# Mecanumbot_Power_Board.net
KiCad netlist of a schematic drawn in EAGLE
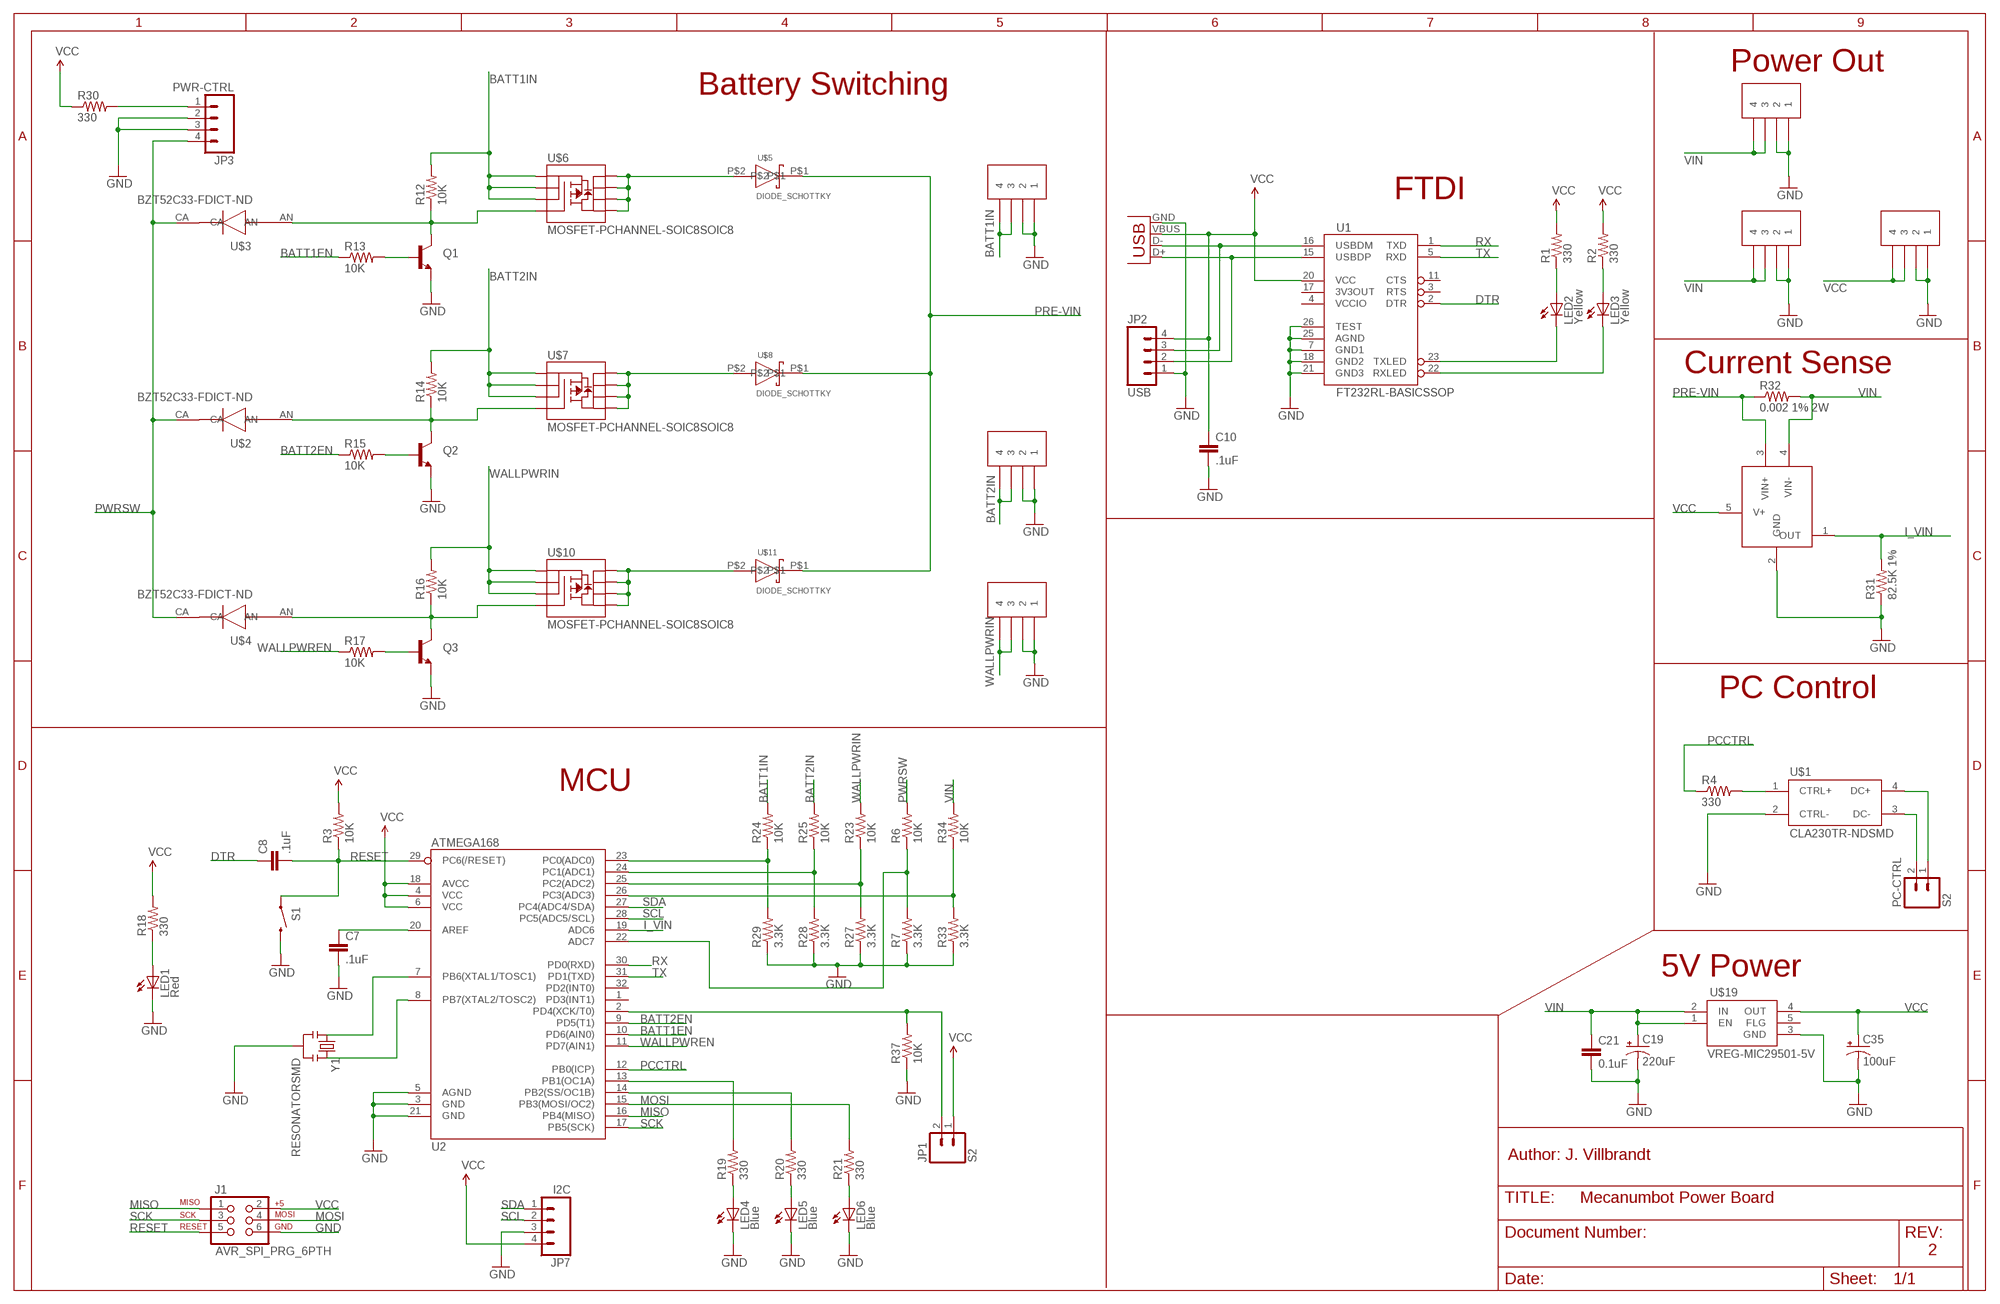
[diagram p0: schematic, sheet 1]

(export (version "E")
  (design (tool "Eeschema 10.0.6"))
  (components
    (comp (ref "C7")
      (value ".1uF")
      (footprint "eagle-import:0603-CAP")
      (libsource (lib "eagle-import") (part "CAP0603-CAP"))
    )
    (comp (ref "C8")
      (value ".1uF")
      (footprint "eagle-import:0603-CAP")
      (libsource (lib "eagle-import") (part "CAP0603-CAP"))
    )
    (comp (ref "C10")
      (value ".1uF")
      (footprint "eagle-import:0603-CAP")
      (libsource (lib "eagle-import") (part "CAP0603-CAP"))
    )
    (comp (ref "C19")
      (value "220uF")
      (footprint "eagle-import:CPOL-RADIAL-1000UF-25V")
      (libsource (lib "eagle-import") (part "SparkFun2_CAP_POLPTH4"))
    )
    (comp (ref "C21")
      (value "0.1uF")
      (footprint "eagle-import:1206")
      (libsource (lib "eagle-import") (part "SparkFun2_CAP1206"))
    )
    (comp (ref "C35")
      (value "100uF")
      (footprint "eagle-import:EIA3216")
      (libsource (lib "eagle-import") (part "CAP_POL1206"))
    )
    (comp (ref "J1")
      (value "AVR_SPI_PRG_6PTH")
      (footprint "eagle-import:2X3")
      (libsource (lib "eagle-import") (part "AVR_SPI_PRG_6PTH"))
    )
    (comp (ref "JP1")
      (value "S2")
      (footprint "eagle-import:1X02")
      (libsource (lib "eagle-import") (part "M02PTH"))
    )
    (comp (ref "JP2")
      (value "USB")
      (footprint "eagle-import:1X04")
      (libsource (lib "eagle-import") (part "M04PTH"))
    )
    (comp (ref "JP3")
      (value "PWR-CTRL")
      (footprint "eagle-import:1X04")
      (libsource (lib "eagle-import") (part "M04PTH"))
    )
    (comp (ref "JP7")
      (value "I2C")
      (footprint "eagle-import:1X04")
      (libsource (lib "eagle-import") (part "M04PTH"))
    )
    (comp (ref "LED1")
      (value "Red")
      (footprint "eagle-import:LED-0603")
      (libsource (lib "eagle-import") (part "LED0603"))
    )
    (comp (ref "LED2")
      (value "Yellow")
      (footprint "eagle-import:LED-0603")
      (libsource (lib "eagle-import") (part "LED0603"))
    )
    (comp (ref "LED3")
      (value "Yellow")
      (footprint "eagle-import:LED-0603")
      (libsource (lib "eagle-import") (part "LED0603"))
    )
    (comp (ref "LED4")
      (value "Blue")
      (footprint "eagle-import:LED-0603")
      (libsource (lib "eagle-import") (part "LED0603"))
    )
    (comp (ref "LED5")
      (value "Blue")
      (footprint "eagle-import:LED-0603")
      (libsource (lib "eagle-import") (part "LED0603"))
    )
    (comp (ref "LED6")
      (value "Blue")
      (footprint "eagle-import:LED-0603")
      (libsource (lib "eagle-import") (part "LED0603"))
    )
    (comp (ref "PC-CTRL")
      (value "S2")
      (footprint "eagle-import:1X02")
      (libsource (lib "eagle-import") (part "M02PTH"))
    )
    (comp (ref "Q1")
      (value "TRANSISTOR_NPNSOT23")
      (footprint "eagle-import:SOT23")
      (libsource (lib "eagle-import") (part "TRANSISTOR_NPNSOT23"))
    )
    (comp (ref "Q2")
      (value "TRANSISTOR_NPNSOT23")
      (footprint "eagle-import:SOT23")
      (libsource (lib "eagle-import") (part "TRANSISTOR_NPNSOT23"))
    )
    (comp (ref "Q3")
      (value "TRANSISTOR_NPNSOT23")
      (footprint "eagle-import:SOT23")
      (libsource (lib "eagle-import") (part "TRANSISTOR_NPNSOT23"))
    )
    (comp (ref "R1")
      (value "330")
      (footprint "eagle-import:0603-RES")
      (libsource (lib "eagle-import") (part "RESISTOR0603-RES"))
    )
    (comp (ref "R2")
      (value "330")
      (footprint "eagle-import:0603-RES")
      (libsource (lib "eagle-import") (part "RESISTOR0603-RES"))
    )
    (comp (ref "R3")
      (value "10K")
      (footprint "eagle-import:0603-RES")
      (libsource (lib "eagle-import") (part "RESISTOR0603-RES"))
    )
    (comp (ref "R4")
      (value "330")
      (footprint "eagle-import:0603-RES")
      (libsource (lib "eagle-import") (part "RESISTOR0603-RES"))
    )
    (comp (ref "R6")
      (value "10K")
      (footprint "eagle-import:0603-RES")
      (libsource (lib "eagle-import") (part "RESISTOR0603-RES"))
    )
    (comp (ref "R7")
      (value "3.3K")
      (footprint "eagle-import:0603-RES")
      (libsource (lib "eagle-import") (part "RESISTOR0603-RES"))
    )
    (comp (ref "R12")
      (value "10K")
      (footprint "eagle-import:0603-RES")
      (libsource (lib "eagle-import") (part "RESISTOR0603-RES"))
    )
    (comp (ref "R13")
      (value "10K")
      (footprint "eagle-import:0603-RES")
      (libsource (lib "eagle-import") (part "RESISTOR0603-RES"))
    )
    (comp (ref "R14")
      (value "10K")
      (footprint "eagle-import:0603-RES")
      (libsource (lib "eagle-import") (part "RESISTOR0603-RES"))
    )
    (comp (ref "R15")
      (value "10K")
      (footprint "eagle-import:0603-RES")
      (libsource (lib "eagle-import") (part "RESISTOR0603-RES"))
    )
    (comp (ref "R16")
      (value "10K")
      (footprint "eagle-import:0603-RES")
      (libsource (lib "eagle-import") (part "RESISTOR0603-RES"))
    )
    (comp (ref "R17")
      (value "10K")
      (footprint "eagle-import:0603-RES")
      (libsource (lib "eagle-import") (part "RESISTOR0603-RES"))
    )
    (comp (ref "R18")
      (value "330")
      (footprint "eagle-import:0603-RES")
      (libsource (lib "eagle-import") (part "RESISTOR0603-RES"))
    )
    (comp (ref "R19")
      (value "330")
      (footprint "eagle-import:0603-RES")
      (libsource (lib "eagle-import") (part "RESISTOR0603-RES"))
    )
    (comp (ref "R20")
      (value "330")
      (footprint "eagle-import:0603-RES")
      (libsource (lib "eagle-import") (part "RESISTOR0603-RES"))
    )
    (comp (ref "R21")
      (value "330")
      (footprint "eagle-import:0603-RES")
      (libsource (lib "eagle-import") (part "RESISTOR0603-RES"))
    )
    (comp (ref "R23")
      (value "10K")
      (footprint "eagle-import:0603-RES")
      (libsource (lib "eagle-import") (part "RESISTOR0603-RES"))
    )
    (comp (ref "R24")
      (value "10K")
      (footprint "eagle-import:0603-RES")
      (libsource (lib "eagle-import") (part "RESISTOR0603-RES"))
    )
    (comp (ref "R25")
      (value "10K")
      (footprint "eagle-import:0603-RES")
      (libsource (lib "eagle-import") (part "RESISTOR0603-RES"))
    )
    (comp (ref "R27")
      (value "3.3K")
      (footprint "eagle-import:0603-RES")
      (libsource (lib "eagle-import") (part "RESISTOR0603-RES"))
    )
    (comp (ref "R28")
      (value "3.3K")
      (footprint "eagle-import:0603-RES")
      (libsource (lib "eagle-import") (part "RESISTOR0603-RES"))
    )
    (comp (ref "R29")
      (value "3.3K")
      (footprint "eagle-import:0603-RES")
      (libsource (lib "eagle-import") (part "RESISTOR0603-RES"))
    )
    (comp (ref "R30")
      (value "330")
      (footprint "eagle-import:0603-RES")
      (libsource (lib "eagle-import") (part "RESISTOR0603-RES"))
    )
    (comp (ref "R31")
      (value "82.5K 1%")
      (footprint "eagle-import:0603-RES")
      (libsource (lib "eagle-import") (part "RESISTOR0603-RES"))
    )
    (comp (ref "R32")
      (value "0.002 1% 2W")
      (footprint "eagle-import:R2512")
      (libsource (lib "eagle-import") (part "RESISTOR2512"))
    )
    (comp (ref "R33")
      (value "3.3K")
      (footprint "eagle-import:0603-RES")
      (libsource (lib "eagle-import") (part "RESISTOR0603-RES"))
    )
    (comp (ref "R34")
      (value "10K")
      (footprint "eagle-import:0603-RES")
      (libsource (lib "eagle-import") (part "RESISTOR0603-RES"))
    )
    (comp (ref "R37")
      (value "10K")
      (footprint "eagle-import:0603-RES")
      (libsource (lib "eagle-import") (part "RESISTOR0603-RES"))
    )
    (comp (ref "S1")
      (value "reset")
      (footprint "eagle-import:TACTILE_SWITCH_SMD")
      (libsource (lib "eagle-import") (part "SWITCH-MOMENTARY-2SMD"))
    )
    (comp (ref "U$1")
      (value "CLA230TR-NDSMD")
      (footprint "eagle-import:4-SOP")
      (libsource (lib "eagle-import") (part "CLA230TR-NDSMD"))
    )
    (comp (ref "U$2")
      (value "BZT52C33-FDICT-ND")
      (footprint "eagle-import:SOD-123")
      (libsource (lib "eagle-import") (part "BZT52C33-FDICT-ND"))
    )
    (comp (ref "U$3")
      (value "BZT52C33-FDICT-ND")
      (footprint "eagle-import:SOD-123")
      (libsource (lib "eagle-import") (part "BZT52C33-FDICT-ND"))
    )
    (comp (ref "U$4")
      (value "BZT52C33-FDICT-ND")
      (footprint "eagle-import:SOD-123")
      (libsource (lib "eagle-import") (part "BZT52C33-FDICT-ND"))
    )
    (comp (ref "U$5")
      (value "DIODE_SCHOTTKY")
      (footprint "eagle-import:DO214AB")
      (libsource (lib "eagle-import") (part "DIODE_SCHOTTKY"))
    )
    (comp (ref "U$6")
      (value "MOSFET-PCHANNEL-SOIC8SOIC8")
      (footprint "eagle-import:SO08")
      (libsource (lib "eagle-import") (part "MOSFET-PCHANNEL-SOIC8SOIC8"))
    )
    (comp (ref "U$7")
      (value "MOSFET-PCHANNEL-SOIC8SOIC8")
      (footprint "eagle-import:SO08")
      (libsource (lib "eagle-import") (part "MOSFET-PCHANNEL-SOIC8SOIC8"))
    )
    (comp (ref "U$8")
      (value "DIODE_SCHOTTKY")
      (footprint "eagle-import:DO214AB")
      (libsource (lib "eagle-import") (part "DIODE_SCHOTTKY"))
    )
    (comp (ref "U$10")
      (value "MOSFET-PCHANNEL-SOIC8SOIC8")
      (footprint "eagle-import:SO08")
      (libsource (lib "eagle-import") (part "MOSFET-PCHANNEL-SOIC8SOIC8"))
    )
    (comp (ref "U$11")
      (value "DIODE_SCHOTTKY")
      (footprint "eagle-import:DO214AB")
      (libsource (lib "eagle-import") (part "DIODE_SCHOTTKY"))
    )
    (comp (ref "U$12")
      (value "TERMINAL-4MINIFIT-JR")
      (footprint "eagle-import:MINIFITJR-RGT-4")
      (libsource (lib "eagle-import") (part "TERMINAL-4MINIFIT-JR"))
    )
    (comp (ref "U$13")
      (value "TERMINAL-4MINIFIT-JR")
      (footprint "eagle-import:MINIFITJR-RGT-4")
      (libsource (lib "eagle-import") (part "TERMINAL-4MINIFIT-JR"))
    )
    (comp (ref "U$14")
      (value "TERMINAL-4MINIFIT-JR")
      (footprint "eagle-import:MINIFITJR-RGT-4")
      (libsource (lib "eagle-import") (part "TERMINAL-4MINIFIT-JR"))
    )
    (comp (ref "U$16")
      (value "TERMINAL-4MINIFIT-JR")
      (footprint "eagle-import:MINIFITJR-RGT-4")
      (libsource (lib "eagle-import") (part "TERMINAL-4MINIFIT-JR"))
    )
    (comp (ref "U$17")
      (value "TERMINAL-4MINIFIT-JR")
      (footprint "eagle-import:MINIFITJR-RGT-4")
      (libsource (lib "eagle-import") (part "TERMINAL-4MINIFIT-JR"))
    )
    (comp (ref "U$18")
      (value "TERMINAL-4MINIFIT-JR")
      (footprint "eagle-import:MINIFITJR-RGT-4")
      (libsource (lib "eagle-import") (part "TERMINAL-4MINIFIT-JR"))
    )
    (comp (ref "U$19")
      (value "VREG-MIC29501-5V")
      (footprint "eagle-import:TO263-5")
      (libsource (lib "eagle-import") (part "VREG-MIC29501-5V"))
    )
    (comp (ref "U$20")
      (value "INA139/169SOT23-5")
      (footprint "eagle-import:SOT23-5")
      (libsource (lib "eagle-import") (part "INA139/169SOT23-5"))
    )
    (comp (ref "U1")
      (value "FT232RL-BASICSSOP")
      (footprint "eagle-import:SSOP28DB")
      (libsource (lib "eagle-import") (part "FT232RL-BASICSSOP"))
    )
    (comp (ref "U2")
      (value "ATMEGA168")
      (footprint "eagle-import:TQFP32-08")
      (libsource (lib "eagle-import") (part "ATMEGA168"))
    )
    (comp (ref "X1")
      (value "USBSMD")
      (footprint "eagle-import:USB-MINIB")
      (libsource (lib "eagle-import") (part "USBSMD"))
    )
    (comp (ref "Y1")
      (value "RESONATORSMD")
      (footprint "eagle-import:RESONATOR-SMD")
      (libsource (lib "eagle-import") (part "RESONATORSMD"))
    )
  )
  (nets
    (net (code "1") (name "/BATT1EN") (class "Default")
      (node (ref "R13") (pin "1") (pinfunction "1_1") (pintype "passive"))
      (node (ref "U2") (pin "10") (pinfunction "PD6(AIN0)_10") (pintype "bidirectional"))
    )
    (net (code "2") (name "/BATT1IN") (class "Default")
      (node (ref "R12") (pin "2") (pinfunction "2_2") (pintype "passive"))
      (node (ref "R24") (pin "2") (pinfunction "2_2") (pintype "passive"))
      (node (ref "U$12") (pin "3") (pinfunction "3_3") (pintype "bidirectional"))
      (node (ref "U$12") (pin "4") (pinfunction "4_4") (pintype "bidirectional"))
      (node (ref "U$6") (pin "1") (pinfunction "S_1") (pintype "bidirectional"))
      (node (ref "U$6") (pin "2") (pinfunction "S_2") (pintype "bidirectional"))
      (node (ref "U$6") (pin "3") (pinfunction "S_3") (pintype "bidirectional"))
    )
    (net (code "3") (name "/BATT2EN") (class "Default")
      (node (ref "R15") (pin "1") (pinfunction "1_1") (pintype "passive"))
      (node (ref "U2") (pin "9") (pinfunction "PD5(T1)_9") (pintype "bidirectional"))
    )
    (net (code "4") (name "/BATT2IN") (class "Default")
      (node (ref "R14") (pin "2") (pinfunction "2_2") (pintype "passive"))
      (node (ref "R25") (pin "2") (pinfunction "2_2") (pintype "passive"))
      (node (ref "U$13") (pin "3") (pinfunction "3_3") (pintype "bidirectional"))
      (node (ref "U$13") (pin "4") (pinfunction "4_4") (pintype "bidirectional"))
      (node (ref "U$7") (pin "1") (pinfunction "S_1") (pintype "bidirectional"))
      (node (ref "U$7") (pin "2") (pinfunction "S_2") (pintype "bidirectional"))
      (node (ref "U$7") (pin "3") (pinfunction "S_3") (pintype "bidirectional"))
    )
    (net (code "5") (name "/DTR") (class "Default")
      (node (ref "C8") (pin "1") (pinfunction "1_1") (pintype "passive"))
      (node (ref "U1") (pin "2") (pinfunction "DTR_2") (pintype "bidirectional"))
    )
    (net (code "6") (name "/I_VIN") (class "Default")
      (node (ref "R31") (pin "2") (pinfunction "2_2") (pintype "passive"))
      (node (ref "U$20") (pin "1") (pinfunction "OUT_1") (pintype "bidirectional"))
      (node (ref "U2") (pin "19") (pinfunction "ADC6_19") (pintype "bidirectional"))
    )
    (net (code "7") (name "/MISO") (class "Default")
      (node (ref "J1") (pin "1") (pinfunction "1_1") (pintype "passive"))
      (node (ref "U2") (pin "16") (pinfunction "PB4(MISO)_16") (pintype "bidirectional"))
    )
    (net (code "8") (name "/MOSI") (class "Default")
      (node (ref "J1") (pin "4") (pinfunction "4_4") (pintype "passive"))
      (node (ref "R21") (pin "2") (pinfunction "2_2") (pintype "passive"))
      (node (ref "U2") (pin "15") (pinfunction "PB3(MOSI/OC2)_15") (pintype "bidirectional"))
    )
    (net (code "9") (name "/PCCTRL") (class "Default")
      (node (ref "R4") (pin "1") (pinfunction "1_1") (pintype "passive"))
      (node (ref "U2") (pin "12") (pinfunction "PB0(ICP)_12") (pintype "bidirectional"))
    )
    (net (code "10") (name "/PRE-VIN") (class "Default")
      (node (ref "R32") (pin "1") (pinfunction "1_1") (pintype "passive"))
      (node (ref "U$11") (pin "P$1") (pinfunction "P$2_P$1") (pintype "bidirectional"))
      (node (ref "U$20") (pin "3") (pinfunction "VIN+_3") (pintype "bidirectional"))
      (node (ref "U$5") (pin "P$1") (pinfunction "P$2_P$1") (pintype "bidirectional"))
      (node (ref "U$8") (pin "P$1") (pinfunction "P$2_P$1") (pintype "bidirectional"))
    )
    (net (code "11") (name "/PWRSW") (class "Default")
      (node (ref "JP3") (pin "4") (pinfunction "4_4") (pintype "passive"))
      (node (ref "R6") (pin "2") (pinfunction "2_2") (pintype "passive"))
      (node (ref "U$2") (pin "CA") (pinfunction "CA_CA") (pintype "bidirectional"))
      (node (ref "U$3") (pin "CA") (pinfunction "CA_CA") (pintype "bidirectional"))
      (node (ref "U$4") (pin "CA") (pinfunction "CA_CA") (pintype "bidirectional"))
    )
    (net (code "12") (name "/RESET") (class "Default")
      (node (ref "C8") (pin "2") (pinfunction "2_2") (pintype "passive"))
      (node (ref "J1") (pin "5") (pinfunction "5_5") (pintype "passive"))
      (node (ref "R3") (pin "1") (pinfunction "1_1") (pintype "passive"))
      (node (ref "S1") (pin "1") (pinfunction "1_1") (pintype "passive"))
      (node (ref "U2") (pin "29") (pinfunction "PC6(/RESET)_29") (pintype "bidirectional"))
    )
    (net (code "13") (name "/RX") (class "Default")
      (node (ref "U1") (pin "1") (pinfunction "TXD_1") (pintype "output"))
      (node (ref "U2") (pin "30") (pinfunction "PD0(RXD)_30") (pintype "bidirectional"))
    )
    (net (code "14") (name "/SCK") (class "Default")
      (node (ref "J1") (pin "3") (pinfunction "3_3") (pintype "passive"))
      (node (ref "U2") (pin "17") (pinfunction "PB5(SCK)_17") (pintype "bidirectional"))
    )
    (net (code "15") (name "/SCL") (class "Default")
      (node (ref "JP7") (pin "2") (pinfunction "2_2") (pintype "passive"))
      (node (ref "U2") (pin "28") (pinfunction "PC5(ADC5/SCL)_28") (pintype "bidirectional"))
    )
    (net (code "16") (name "/SDA") (class "Default")
      (node (ref "JP7") (pin "1") (pinfunction "1_1") (pintype "passive"))
      (node (ref "U2") (pin "27") (pinfunction "PC4(ADC4/SDA)_27") (pintype "bidirectional"))
    )
    (net (code "17") (name "/TX") (class "Default")
      (node (ref "U1") (pin "5") (pinfunction "RXD_5") (pintype "input"))
      (node (ref "U2") (pin "31") (pinfunction "PD1(TXD)_31") (pintype "bidirectional"))
    )
    (net (code "18") (name "/VCCIO") (class "Default")
      (node (ref "U1") (pin "4") (pinfunction "VCCIO_4") (pintype "power_in"))
    )
    (net (code "19") (name "/VIN") (class "Default")
      (node (ref "C19") (pin "1") (pinfunction "+_1") (pintype "passive"))
      (node (ref "C21") (pin "1") (pinfunction "1_1") (pintype "passive"))
      (node (ref "R32") (pin "2") (pinfunction "2_2") (pintype "passive"))
      (node (ref "R34") (pin "2") (pinfunction "2_2") (pintype "passive"))
      (node (ref "U$16") (pin "3") (pinfunction "3_3") (pintype "bidirectional"))
      (node (ref "U$16") (pin "4") (pinfunction "4_4") (pintype "bidirectional"))
      (node (ref "U$17") (pin "3") (pinfunction "3_3") (pintype "bidirectional"))
      (node (ref "U$17") (pin "4") (pinfunction "4_4") (pintype "bidirectional"))
      (node (ref "U$19") (pin "1") (pinfunction "EN_1") (pintype "input"))
      (node (ref "U$19") (pin "2") (pinfunction "IN_2") (pintype "input"))
      (node (ref "U$20") (pin "4") (pinfunction "VIN-_4") (pintype "bidirectional"))
    )
    (net (code "20") (name "/WALLPWREN") (class "Default")
      (node (ref "R17") (pin "1") (pinfunction "1_1") (pintype "passive"))
      (node (ref "U2") (pin "11") (pinfunction "PD7(AIN1)_11") (pintype "bidirectional"))
    )
    (net (code "21") (name "/WALLPWRIN") (class "Default")
      (node (ref "R16") (pin "2") (pinfunction "2_2") (pintype "passive"))
      (node (ref "R23") (pin "2") (pinfunction "2_2") (pintype "passive"))
      (node (ref "U$10") (pin "1") (pinfunction "S_1") (pintype "bidirectional"))
      (node (ref "U$10") (pin "2") (pinfunction "S_2") (pintype "bidirectional"))
      (node (ref "U$10") (pin "3") (pinfunction "S_3") (pintype "bidirectional"))
      (node (ref "U$14") (pin "3") (pinfunction "3_3") (pintype "bidirectional"))
      (node (ref "U$14") (pin "4") (pinfunction "4_4") (pintype "bidirectional"))
    )
    (net (code "22") (name "GND") (class "Default")
      (node (ref "C10") (pin "2") (pinfunction "2_2") (pintype "passive"))
      (node (ref "C19") (pin "2") (pinfunction "-_2") (pintype "passive"))
      (node (ref "C21") (pin "2") (pinfunction "2_2") (pintype "passive"))
      (node (ref "C35") (pin "C") (pinfunction "-_C") (pintype "passive"))
      (node (ref "C7") (pin "2") (pinfunction "2_2") (pintype "passive"))
      (node (ref "J1") (pin "6") (pinfunction "6_6") (pintype "passive"))
      (node (ref "JP2") (pin "1") (pinfunction "1_1") (pintype "passive"))
      (node (ref "JP3") (pin "2") (pinfunction "2_2") (pintype "passive"))
      (node (ref "JP3") (pin "3") (pinfunction "3_3") (pintype "passive"))
      (node (ref "JP7") (pin "3") (pinfunction "3_3") (pintype "passive"))
      (node (ref "LED1") (pin "C") (pinfunction "C_C") (pintype "passive"))
      (node (ref "LED4") (pin "C") (pinfunction "C_C") (pintype "passive"))
      (node (ref "LED5") (pin "C") (pinfunction "C_C") (pintype "passive"))
      (node (ref "LED6") (pin "C") (pinfunction "C_C") (pintype "passive"))
      (node (ref "Q1") (pin "2") (pinfunction "E_2") (pintype "passive"))
      (node (ref "Q2") (pin "2") (pinfunction "E_2") (pintype "passive"))
      (node (ref "Q3") (pin "2") (pinfunction "E_2") (pintype "passive"))
      (node (ref "R27") (pin "1") (pinfunction "1_1") (pintype "passive"))
      (node (ref "R28") (pin "1") (pinfunction "1_1") (pintype "passive"))
      (node (ref "R29") (pin "1") (pinfunction "1_1") (pintype "passive"))
      (node (ref "R31") (pin "1") (pinfunction "1_1") (pintype "passive"))
      (node (ref "R33") (pin "1") (pinfunction "1_1") (pintype "passive"))
      (node (ref "R37") (pin "1") (pinfunction "1_1") (pintype "passive"))
      (node (ref "R7") (pin "1") (pinfunction "1_1") (pintype "passive"))
      (node (ref "S1") (pin "3") (pinfunction "2_3") (pintype "passive"))
      (node (ref "U$1") (pin "2") (pinfunction "CTRL-_2") (pintype "bidirectional"))
      (node (ref "U$12") (pin "1") (pinfunction "1_1") (pintype "bidirectional"))
      (node (ref "U$12") (pin "2") (pinfunction "2_2") (pintype "bidirectional"))
      (node (ref "U$13") (pin "1") (pinfunction "1_1") (pintype "bidirectional"))
      (node (ref "U$13") (pin "2") (pinfunction "2_2") (pintype "bidirectional"))
      (node (ref "U$14") (pin "1") (pinfunction "1_1") (pintype "bidirectional"))
      (node (ref "U$14") (pin "2") (pinfunction "2_2") (pintype "bidirectional"))
      (node (ref "U$16") (pin "1") (pinfunction "1_1") (pintype "bidirectional"))
      (node (ref "U$16") (pin "2") (pinfunction "2_2") (pintype "bidirectional"))
      (node (ref "U$17") (pin "1") (pinfunction "1_1") (pintype "bidirectional"))
      (node (ref "U$17") (pin "2") (pinfunction "2_2") (pintype "bidirectional"))
      (node (ref "U$18") (pin "1") (pinfunction "1_1") (pintype "bidirectional"))
      (node (ref "U$18") (pin "2") (pinfunction "2_2") (pintype "bidirectional"))
      (node (ref "U$19") (pin "3") (pinfunction "GND_3") (pintype "input"))
      (node (ref "U$20") (pin "2") (pinfunction "GND_2") (pintype "bidirectional"))
      (node (ref "U1") (pin "18") (pinfunction "GND2_18") (pintype "power_in"))
      (node (ref "U1") (pin "21") (pinfunction "GND3_21") (pintype "power_in"))
      (node (ref "U1") (pin "25") (pinfunction "AGND_25") (pintype "power_in"))
      (node (ref "U1") (pin "26") (pinfunction "TEST_26") (pintype "input"))
      (node (ref "U1") (pin "7") (pinfunction "GND1_7") (pintype "power_in"))
      (node (ref "U2") (pin "21") (pinfunction "GND_21") (pintype "bidirectional"))
      (node (ref "U2") (pin "3") (pinfunction "GND_3") (pintype "bidirectional"))
      (node (ref "U2") (pin "5") (pinfunction "AGND_5") (pintype "bidirectional"))
      (node (ref "X1") (pin "GND") (pinfunction "GND_GND") (pintype "bidirectional"))
      (node (ref "Y1") (pin "2") (pinfunction "2_2") (pintype "passive"))
    )
    (net (code "23") (name "Net-(JP3-Pad1)") (class "Default")
      (node (ref "JP3") (pin "1") (pinfunction "1_1") (pintype "passive"))
      (node (ref "R30") (pin "2") (pinfunction "2_2") (pintype "passive"))
    )
    (net (code "24") (name "Net-(LED1-PadA)") (class "Default")
      (node (ref "LED1") (pin "A") (pinfunction "A_A") (pintype "passive"))
      (node (ref "R18") (pin "1") (pinfunction "1_1") (pintype "passive"))
    )
    (net (code "25") (name "Net-(LED2-PadA)") (class "Default")
      (node (ref "LED2") (pin "A") (pinfunction "A_A") (pintype "passive"))
      (node (ref "R1") (pin "1") (pinfunction "1_1") (pintype "passive"))
    )
    (net (code "26") (name "Net-(LED3-PadA)") (class "Default")
      (node (ref "LED3") (pin "A") (pinfunction "A_A") (pintype "passive"))
      (node (ref "R2") (pin "1") (pinfunction "1_1") (pintype "passive"))
    )
    (net (code "27") (name "Net-(LED4-PadA)") (class "Default")
      (node (ref "LED4") (pin "A") (pinfunction "A_A") (pintype "passive"))
      (node (ref "R19") (pin "1") (pinfunction "1_1") (pintype "passive"))
    )
    (net (code "28") (name "Net-(LED5-PadA)") (class "Default")
      (node (ref "LED5") (pin "A") (pinfunction "A_A") (pintype "passive"))
      (node (ref "R20") (pin "1") (pinfunction "1_1") (pintype "passive"))
    )
    (net (code "29") (name "Net-(LED6-PadA)") (class "Default")
      (node (ref "LED6") (pin "A") (pinfunction "A_A") (pintype "passive"))
      (node (ref "R21") (pin "1") (pinfunction "1_1") (pintype "passive"))
    )
    (net (code "30") (name "Net-(Q1-B)") (class "Default")
      (node (ref "Q1") (pin "1") (pinfunction "B_1") (pintype "passive"))
      (node (ref "R13") (pin "2") (pinfunction "2_2") (pintype "passive"))
    )
    (net (code "31") (name "Net-(Q1-C)") (class "Default")
      (node (ref "Q1") (pin "3") (pinfunction "C_3") (pintype "passive"))
      (node (ref "R12") (pin "1") (pinfunction "1_1") (pintype "passive"))
      (node (ref "U$3") (pin "AN") (pinfunction "AN_AN") (pintype "bidirectional"))
      (node (ref "U$6") (pin "4") (pinfunction "G_4") (pintype "bidirectional"))
    )
    (net (code "32") (name "Net-(Q2-B)") (class "Default")
      (node (ref "Q2") (pin "1") (pinfunction "B_1") (pintype "passive"))
      (node (ref "R15") (pin "2") (pinfunction "2_2") (pintype "passive"))
    )
    (net (code "33") (name "Net-(Q2-C)") (class "Default")
      (node (ref "Q2") (pin "3") (pinfunction "C_3") (pintype "passive"))
      (node (ref "R14") (pin "1") (pinfunction "1_1") (pintype "passive"))
      (node (ref "U$2") (pin "AN") (pinfunction "AN_AN") (pintype "bidirectional"))
      (node (ref "U$7") (pin "4") (pinfunction "G_4") (pintype "bidirectional"))
    )
    (net (code "34") (name "Net-(Q3-B)") (class "Default")
      (node (ref "Q3") (pin "1") (pinfunction "B_1") (pintype "passive"))
      (node (ref "R17") (pin "2") (pinfunction "2_2") (pintype "passive"))
    )
    (net (code "35") (name "Net-(Q3-C)") (class "Default")
      (node (ref "Q3") (pin "3") (pinfunction "C_3") (pintype "passive"))
      (node (ref "R16") (pin "1") (pinfunction "1_1") (pintype "passive"))
      (node (ref "U$10") (pin "4") (pinfunction "G_4") (pintype "bidirectional"))
      (node (ref "U$4") (pin "AN") (pinfunction "AN_AN") (pintype "bidirectional"))
    )
    (net (code "36") (name "Net-(U$1-CTRL+)") (class "Default")
      (node (ref "R4") (pin "2") (pinfunction "2_2") (pintype "passive"))
      (node (ref "U$1") (pin "1") (pinfunction "CTRL+_1") (pintype "bidirectional"))
    )
    (net (code "37") (name "Net-(U$1-DC+)") (class "Default")
      (node (ref "PC-CTRL") (pin "1") (pinfunction "1_1") (pintype "passive"))
      (node (ref "U$1") (pin "4") (pinfunction "DC+_4") (pintype "bidirectional"))
    )
    (net (code "38") (name "Net-(U$1-DC-)") (class "Default")
      (node (ref "PC-CTRL") (pin "2") (pinfunction "2_2") (pintype "passive"))
      (node (ref "U$1") (pin "3") (pinfunction "DC-_3") (pintype "bidirectional"))
    )
    (net (code "39") (name "Net-(U$5-P$1)") (class "Default")
      (node (ref "U$5") (pin "P$2") (pinfunction "P$1_P$2") (pintype "bidirectional"))
      (node (ref "U$6") (pin "5") (pinfunction "D_5") (pintype "bidirectional"))
      (node (ref "U$6") (pin "6") (pinfunction "D_6") (pintype "bidirectional"))
      (node (ref "U$6") (pin "7") (pinfunction "D_7") (pintype "bidirectional"))
      (node (ref "U$6") (pin "8") (pinfunction "D_8") (pintype "bidirectional"))
    )
    (net (code "40") (name "Net-(U$8-P$1)") (class "Default")
      (node (ref "U$7") (pin "5") (pinfunction "D_5") (pintype "bidirectional"))
      (node (ref "U$7") (pin "6") (pinfunction "D_6") (pintype "bidirectional"))
      (node (ref "U$7") (pin "7") (pinfunction "D_7") (pintype "bidirectional"))
      (node (ref "U$7") (pin "8") (pinfunction "D_8") (pintype "bidirectional"))
      (node (ref "U$8") (pin "P$2") (pinfunction "P$1_P$2") (pintype "bidirectional"))
    )
    (net (code "41") (name "Net-(U$11-P$1)") (class "Default")
      (node (ref "U$10") (pin "5") (pinfunction "D_5") (pintype "bidirectional"))
      (node (ref "U$10") (pin "6") (pinfunction "D_6") (pintype "bidirectional"))
      (node (ref "U$10") (pin "7") (pinfunction "D_7") (pintype "bidirectional"))
      (node (ref "U$10") (pin "8") (pinfunction "D_8") (pintype "bidirectional"))
      (node (ref "U$11") (pin "P$2") (pinfunction "P$1_P$2") (pintype "bidirectional"))
    )
    (net (code "42") (name "Net-(U1-RXLED)") (class "Default")
      (node (ref "LED3") (pin "C") (pinfunction "C_C") (pintype "passive"))
      (node (ref "U1") (pin "22") (pinfunction "RXLED_22") (pintype "bidirectional"))
    )
    (net (code "43") (name "Net-(U1-TXLED)") (class "Default")
      (node (ref "LED2") (pin "C") (pinfunction "C_C") (pintype "passive"))
      (node (ref "U1") (pin "23") (pinfunction "TXLED_23") (pintype "bidirectional"))
    )
    (net (code "44") (name "Net-(U1-USBDM)") (class "Default")
      (node (ref "JP2") (pin "3") (pinfunction "3_3") (pintype "passive"))
      (node (ref "U1") (pin "16") (pinfunction "USBDM_16") (pintype "bidirectional"))
      (node (ref "X1") (pin "D-") (pinfunction "D-_D-") (pintype "bidirectional"))
    )
    (net (code "45") (name "Net-(U1-USBDP)") (class "Default")
      (node (ref "JP2") (pin "2") (pinfunction "2_2") (pintype "passive"))
      (node (ref "U1") (pin "15") (pinfunction "USBDP_15") (pintype "bidirectional"))
      (node (ref "X1") (pin "D+") (pinfunction "D+_D+") (pintype "bidirectional"))
    )
    (net (code "46") (name "Net-(U2-ADC7)") (class "Default")
      (node (ref "R6") (pin "1") (pinfunction "1_1") (pintype "passive"))
      (node (ref "R7") (pin "2") (pinfunction "2_2") (pintype "passive"))
      (node (ref "U2") (pin "22") (pinfunction "ADC7_22") (pintype "bidirectional"))
    )
    (net (code "47") (name "Net-(U2-AREF)") (class "Default")
      (node (ref "C7") (pin "1") (pinfunction "1_1") (pintype "passive"))
      (node (ref "U2") (pin "20") (pinfunction "AREF_20") (pintype "bidirectional"))
    )
    (net (code "48") (name "Net-(U2-PB1(OC1A))") (class "Default")
      (node (ref "R19") (pin "2") (pinfunction "2_2") (pintype "passive"))
      (node (ref "U2") (pin "13") (pinfunction "PB1(OC1A)_13") (pintype "bidirectional"))
    )
    (net (code "49") (name "Net-(U2-PB2(SS{slash}OC1B))") (class "Default")
      (node (ref "R20") (pin "2") (pinfunction "2_2") (pintype "passive"))
      (node (ref "U2") (pin "14") (pinfunction "PB2(SS/OC1B)_14") (pintype "bidirectional"))
    )
    (net (code "50") (name "Net-(U2-PB6(XTAL1{slash}TOSC1))") (class "Default")
      (node (ref "U2") (pin "7") (pinfunction "PB6(XTAL1/TOSC1)_7") (pintype "bidirectional"))
      (node (ref "Y1") (pin "1") (pinfunction "1_1") (pintype "passive"))
    )
    (net (code "51") (name "Net-(U2-PB7(XTAL2{slash}TOSC2))") (class "Default")
      (node (ref "U2") (pin "8") (pinfunction "PB7(XTAL2/TOSC2)_8") (pintype "bidirectional"))
      (node (ref "Y1") (pin "3") (pinfunction "3_3") (pintype "passive"))
    )
    (net (code "52") (name "Net-(U2-PC0(ADC0))") (class "Default")
      (node (ref "R24") (pin "1") (pinfunction "1_1") (pintype "passive"))
      (node (ref "R29") (pin "2") (pinfunction "2_2") (pintype "passive"))
      (node (ref "U2") (pin "23") (pinfunction "PC0(ADC0)_23") (pintype "bidirectional"))
    )
    (net (code "53") (name "Net-(U2-PC1(ADC1))") (class "Default")
      (node (ref "R25") (pin "1") (pinfunction "1_1") (pintype "passive"))
      (node (ref "R28") (pin "2") (pinfunction "2_2") (pintype "passive"))
      (node (ref "U2") (pin "24") (pinfunction "PC1(ADC1)_24") (pintype "bidirectional"))
    )
    (net (code "54") (name "Net-(U2-PC2(ADC2))") (class "Default")
      (node (ref "R23") (pin "1") (pinfunction "1_1") (pintype "passive"))
      (node (ref "R27") (pin "2") (pinfunction "2_2") (pintype "passive"))
      (node (ref "U2") (pin "25") (pinfunction "PC2(ADC2)_25") (pintype "bidirectional"))
    )
    (net (code "55") (name "Net-(U2-PC3(ADC3))") (class "Default")
      (node (ref "R33") (pin "2") (pinfunction "2_2") (pintype "passive"))
      (node (ref "R34") (pin "1") (pinfunction "1_1") (pintype "passive"))
      (node (ref "U2") (pin "26") (pinfunction "PC3(ADC3)_26") (pintype "bidirectional"))
    )
    (net (code "56") (name "Net-(U2-PD4(XCK{slash}T0))") (class "Default")
      (node (ref "JP1") (pin "2") (pinfunction "2_2") (pintype "passive"))
      (node (ref "R37") (pin "2") (pinfunction "2_2") (pintype "passive"))
      (node (ref "U2") (pin "2") (pinfunction "PD4(XCK/T0)_2") (pintype "bidirectional"))
    )
    (net (code "57") (name "VCC") (class "Default")
      (node (ref "C10") (pin "1") (pinfunction "1_1") (pintype "passive"))
      (node (ref "C35") (pin "A") (pinfunction "+_A") (pintype "passive"))
      (node (ref "J1") (pin "2") (pinfunction "2_2") (pintype "passive"))
      (node (ref "JP1") (pin "1") (pinfunction "1_1") (pintype "passive"))
      (node (ref "JP2") (pin "4") (pinfunction "4_4") (pintype "passive"))
      (node (ref "JP7") (pin "4") (pinfunction "4_4") (pintype "passive"))
      (node (ref "R1") (pin "2") (pinfunction "2_2") (pintype "passive"))
      (node (ref "R18") (pin "2") (pinfunction "2_2") (pintype "passive"))
      (node (ref "R2") (pin "2") (pinfunction "2_2") (pintype "passive"))
      (node (ref "R3") (pin "2") (pinfunction "2_2") (pintype "passive"))
      (node (ref "R30") (pin "1") (pinfunction "1_1") (pintype "passive"))
      (node (ref "U$18") (pin "3") (pinfunction "3_3") (pintype "bidirectional"))
      (node (ref "U$18") (pin "4") (pinfunction "4_4") (pintype "bidirectional"))
      (node (ref "U$19") (pin "4") (pinfunction "OUT_4") (pintype "input"))
      (node (ref "U$20") (pin "5") (pinfunction "V+_5") (pintype "bidirectional"))
      (node (ref "U1") (pin "20") (pinfunction "VCC_20") (pintype "power_in"))
      (node (ref "U2") (pin "18") (pinfunction "AVCC_18") (pintype "bidirectional"))
      (node (ref "U2") (pin "4") (pinfunction "VCC_4") (pintype "bidirectional"))
      (node (ref "U2") (pin "6") (pinfunction "VCC_6") (pintype "bidirectional"))
      (node (ref "X1") (pin "VBUS") (pinfunction "VBUS_VBUS") (pintype "bidirectional"))
    )
    (net (code "58") (name "unconnected-(U$19-FLG-Pad5)") (class "Default")
      (node (ref "U$19") (pin "5") (pinfunction "FLG_5") (pintype "input"))
    )
    (net (code "59") (name "unconnected-(U1-3V3OUT-Pad17)") (class "Default")
      (node (ref "U1") (pin "17") (pinfunction "3V3OUT_17") (pintype "output"))
    )
    (net (code "60") (name "unconnected-(U1-CTS-Pad11)") (class "Default")
      (node (ref "U1") (pin "11") (pinfunction "CTS_11") (pintype "bidirectional"))
    )
    (net (code "61") (name "unconnected-(U1-RTS-Pad3)") (class "Default")
      (node (ref "U1") (pin "3") (pinfunction "RTS_3") (pintype "bidirectional"))
    )
    (net (code "62") (name "unconnected-(U2-PD2(INT0)-Pad32)") (class "Default")
      (node (ref "U2") (pin "32") (pinfunction "PD2(INT0)_32") (pintype "bidirectional"))
    )
    (net (code "63") (name "unconnected-(U2-PD3(INT1)-Pad1)") (class "Default")
      (node (ref "U2") (pin "1") (pinfunction "PD3(INT1)_1") (pintype "bidirectional"))
    )
  )
)
